# MX1508_H-bridge.net
KiCad netlist of a schematic drawn in EAGLE
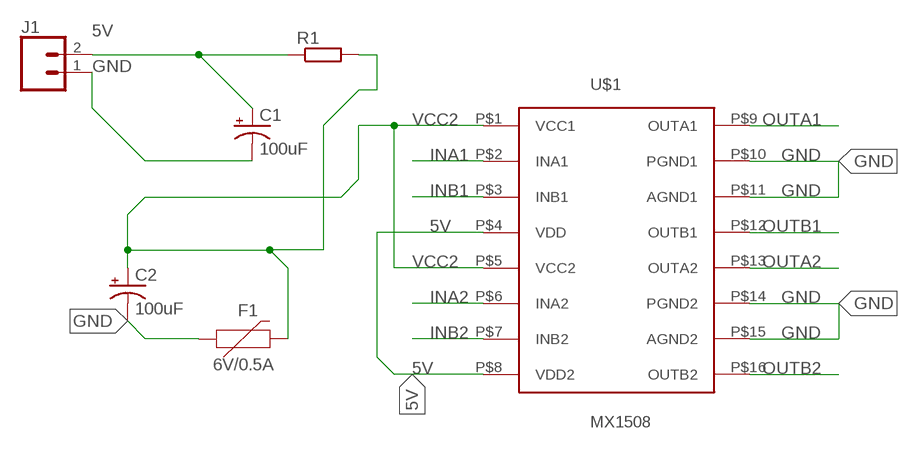
[diagram p0: schematic, sheet 1]

(export (version "E")
  (design (tool "Eeschema 10.0.6"))
  (components
    (comp (ref "C1")
      (value "100uF")
      (footprint "eagle-import:NIC_10X10.5_CAP")
      (libsource (lib "eagle-import") (part "100UF-POLAR-10X10.5-63V-20%"))
    )
    (comp (ref "C2")
      (value "100uF")
      (footprint "eagle-import:NIC_10X10.5_CAP")
      (libsource (lib "eagle-import") (part "100UF-POLAR-10X10.5-63V-20%"))
    )
    (comp (ref "F1")
      (value "6V/0.5A")
      (footprint "eagle-import:1206")
      (libsource (lib "eagle-import") (part "PPTC_HALF-AMP"))
    )
    (comp (ref "J1")
      (value "CONN_02")
      (footprint "eagle-import:1X02")
      (libsource (lib "eagle-import") (part "CONN_02"))
    )
    (comp (ref "R1")
      (value "R-EU_M0805")
      (footprint "eagle-import:M0805")
      (libsource (lib "eagle-import") (part "R-EU_M0805"))
    )
    (comp (ref "U$1")
      (value "MX1508")
      (footprint "eagle-import:MX1508")
      (libsource (lib "eagle-import") (part "MX1508"))
    )
  )
  (nets
    (net (code "1") (name "/INA1") (class "Default")
      (node (ref "U$1") (pin "P$2") (pinfunction "INA1_P$2") (pintype "bidirectional"))
    )
    (net (code "2") (name "/INA2") (class "Default")
      (node (ref "U$1") (pin "P$6") (pinfunction "INA2_P$6") (pintype "bidirectional"))
    )
    (net (code "3") (name "/INB1") (class "Default")
      (node (ref "U$1") (pin "P$3") (pinfunction "INB1_P$3") (pintype "bidirectional"))
    )
    (net (code "4") (name "/INB2") (class "Default")
      (node (ref "U$1") (pin "P$7") (pinfunction "INB2_P$7") (pintype "bidirectional"))
    )
    (net (code "5") (name "/OUTA1") (class "Default")
      (node (ref "U$1") (pin "P$9") (pinfunction "OUTA1_P$9") (pintype "bidirectional"))
    )
    (net (code "6") (name "/OUTA2") (class "Default")
      (node (ref "U$1") (pin "P$13") (pinfunction "OUTA2_P$13") (pintype "bidirectional"))
    )
    (net (code "7") (name "/OUTB1") (class "Default")
      (node (ref "U$1") (pin "P$12") (pinfunction "OUTB1_P$12") (pintype "bidirectional"))
    )
    (net (code "8") (name "/OUTB2") (class "Default")
      (node (ref "U$1") (pin "P$16") (pinfunction "OUTB2_P$16") (pintype "bidirectional"))
    )
    (net (code "9") (name "/VCC2") (class "Default")
      (node (ref "C2") (pin "+") (pinfunction "+_+") (pintype "passive"))
      (node (ref "F1") (pin "2") (pinfunction "2_2") (pintype "bidirectional"))
      (node (ref "R1") (pin "2") (pinfunction "2_2") (pintype "passive"))
      (node (ref "U$1") (pin "P$1") (pinfunction "VCC1_P$1") (pintype "bidirectional"))
      (node (ref "U$1") (pin "P$5") (pinfunction "VCC2_P$5") (pintype "bidirectional"))
    )
    (net (code "10") (name "5V") (class "Default")
      (node (ref "C1") (pin "+") (pinfunction "+_+") (pintype "passive"))
      (node (ref "J1") (pin "2") (pinfunction "2_2") (pintype "passive"))
      (node (ref "R1") (pin "1") (pinfunction "1_1") (pintype "passive"))
      (node (ref "U$1") (pin "P$4") (pinfunction "VDD_P$4") (pintype "bidirectional"))
      (node (ref "U$1") (pin "P$8") (pinfunction "VDD2_P$8") (pintype "bidirectional"))
    )
    (net (code "11") (name "GND") (class "Default")
      (node (ref "C1") (pin "-") (pinfunction "-_-") (pintype "passive"))
      (node (ref "C2") (pin "-") (pinfunction "-_-") (pintype "passive"))
      (node (ref "F1") (pin "1") (pinfunction "1_1") (pintype "bidirectional"))
      (node (ref "J1") (pin "1") (pinfunction "1_1") (pintype "passive"))
      (node (ref "U$1") (pin "P$10") (pinfunction "PGND1_P$10") (pintype "bidirectional"))
      (node (ref "U$1") (pin "P$11") (pinfunction "AGND1_P$11") (pintype "bidirectional"))
      (node (ref "U$1") (pin "P$14") (pinfunction "PGND2_P$14") (pintype "bidirectional"))
      (node (ref "U$1") (pin "P$15") (pinfunction "AGND2_P$15") (pintype "bidirectional"))
    )
  )
)
